# SCH_PIF_Line_Follower_2024-01-01_1.net
KiCad netlist of a schematic drawn in EasyEDA
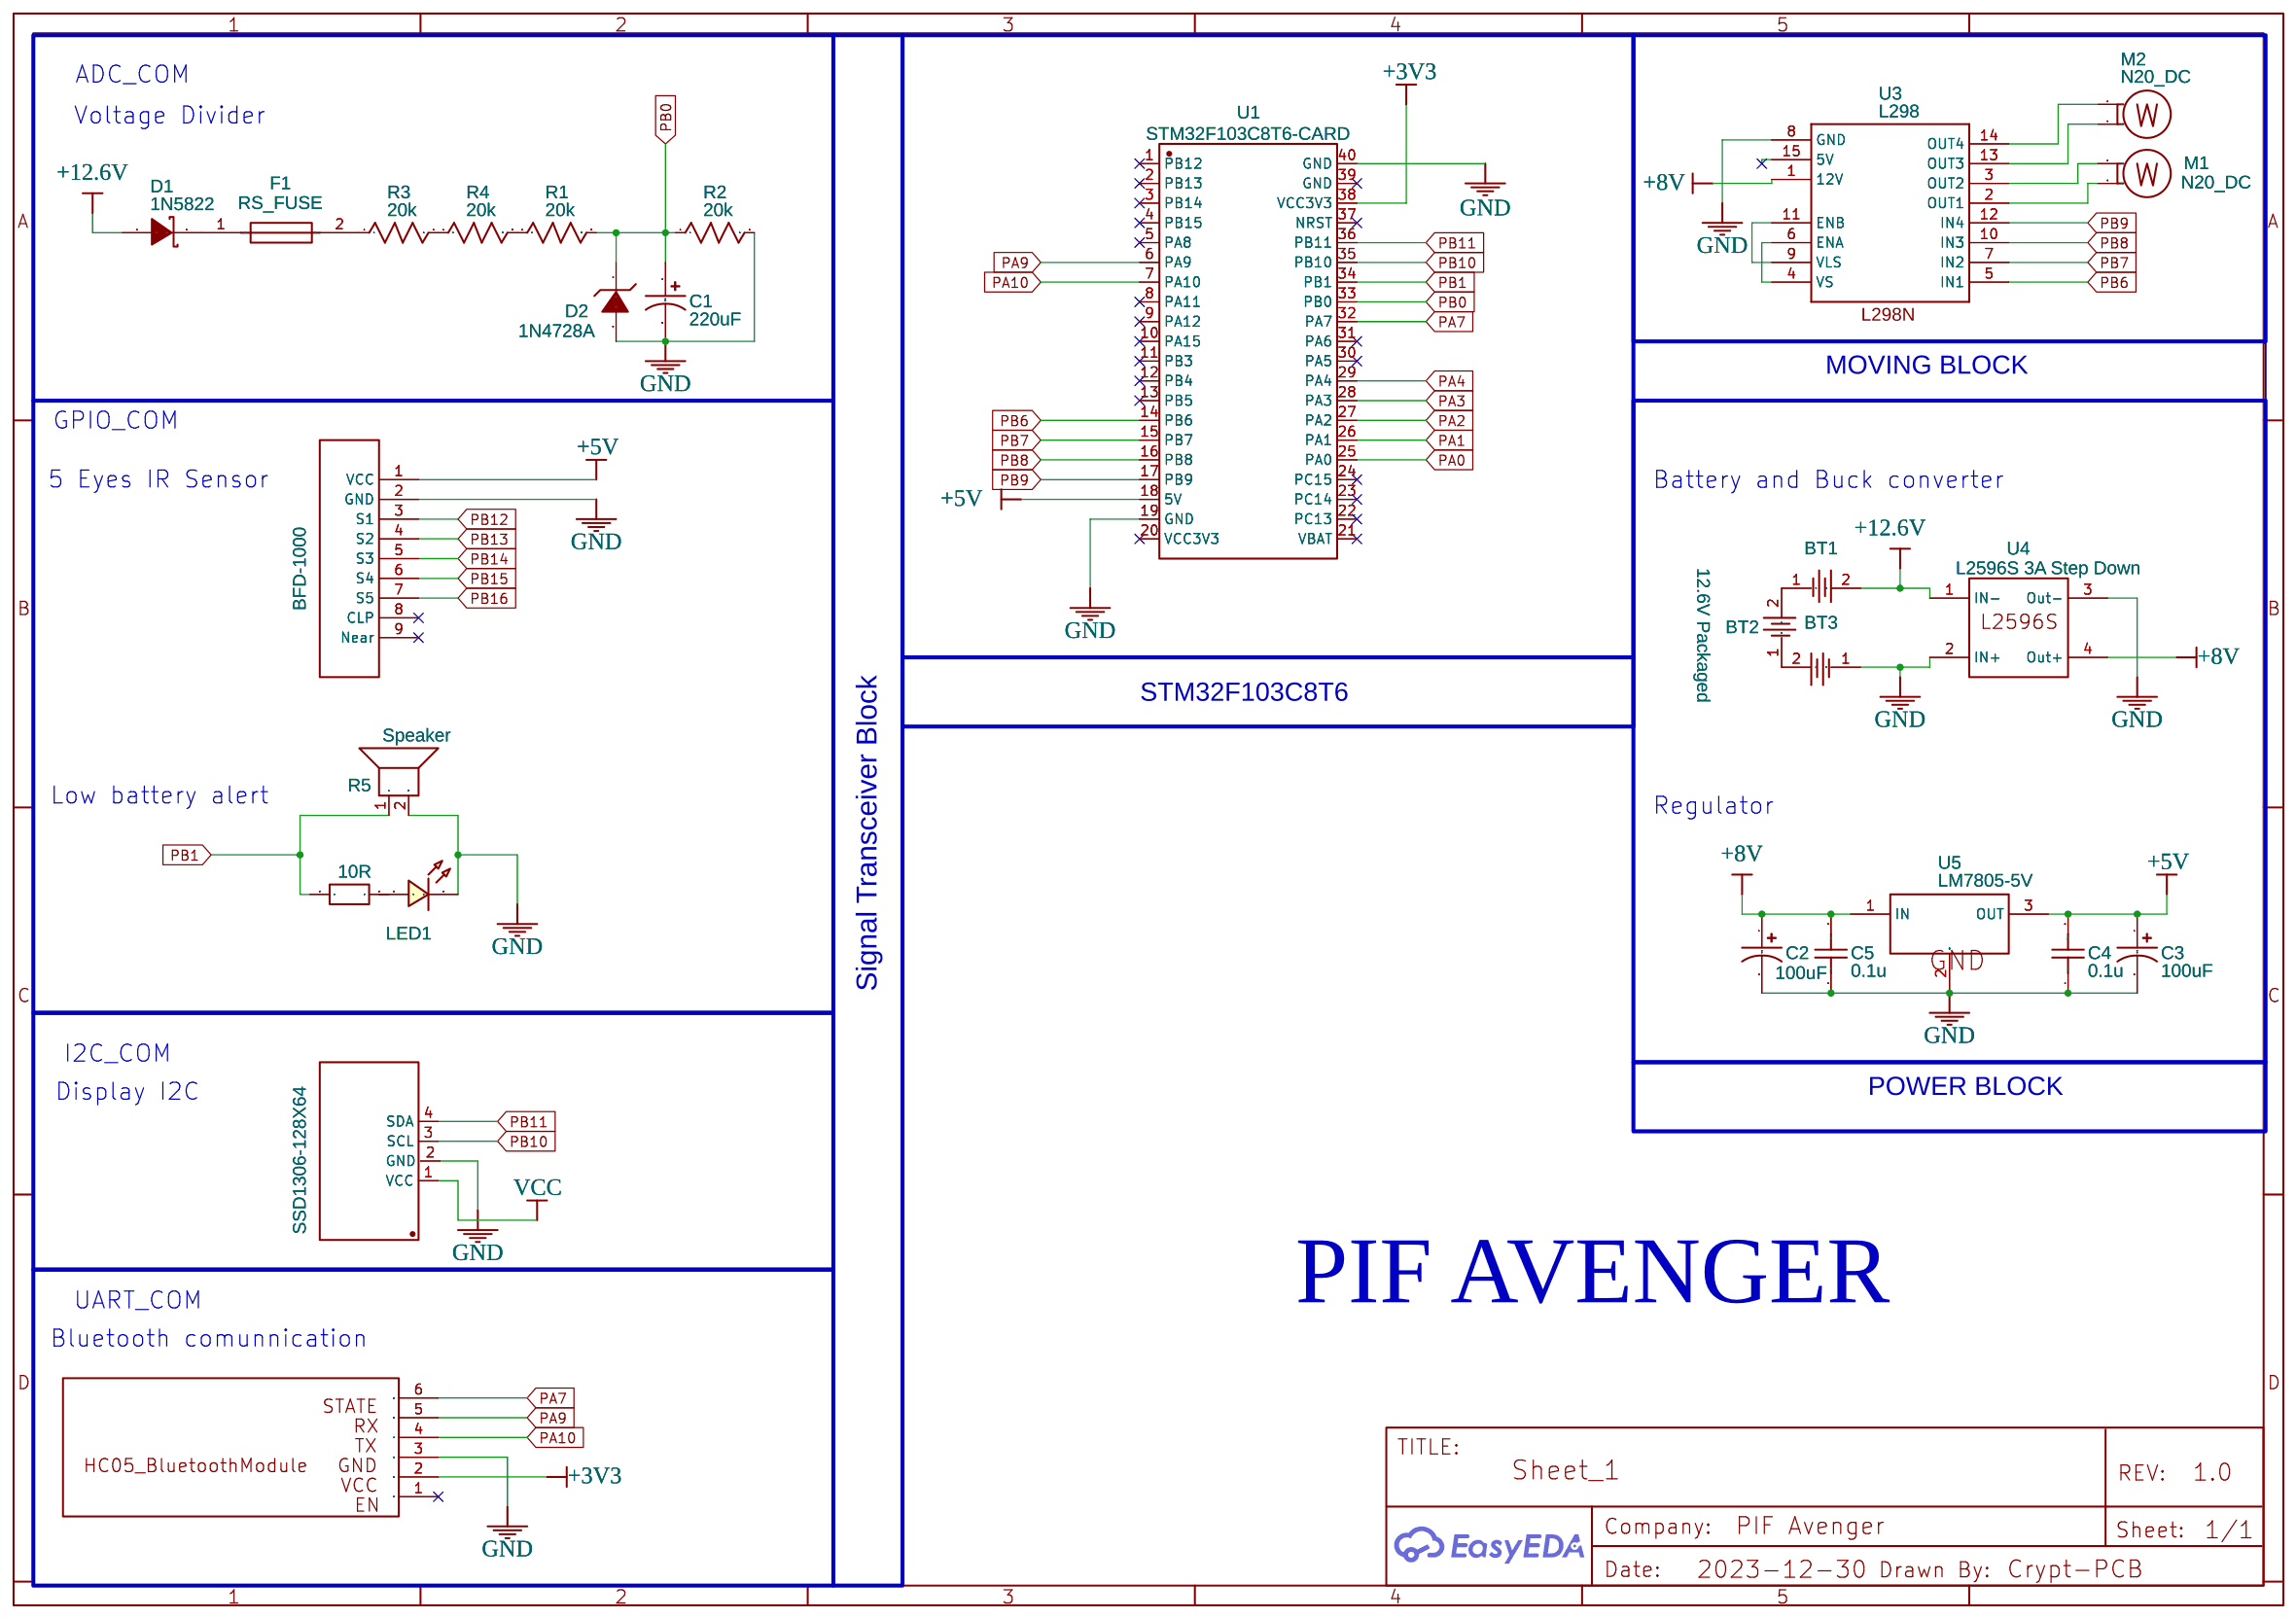
[diagram p0: schematic sheet]

(export (version "E")
  (design (tool "Eeschema 10.0.6"))
  (components
    (comp (ref "BT1")
      (value "BH-18650-A1AJ006")
      (fields (field (name "Manufacturer") "MYOUNG(美阳)"))
      (libsource (lib "") (part "BH-18650-A1AJ006_1"))
    )
    (comp (ref "BT2")
      (value "12.6V Packaged")
      (fields
        (field (name "Manufacturer Part") "BH-18650-A1AJ006")
        (field (name "Manufacturer") "MYOUNG(美阳)")
      )
      (libsource (lib "") (part "BH-18650-A1AJ006"))
    )
    (comp (ref "BT3")
      (value "BH-18650-A1AJ006")
      (fields (field (name "Manufacturer") "MYOUNG(美阳)"))
      (libsource (lib "") (part "BH-18650-A1AJ006_2"))
    )
    (comp (ref "C1") (value "220uF") (libsource (lib "") (part "CE_TH_D4.0×F1.5_US")))
    (comp (ref "C2") (value "100uF") (libsource (lib "") (part "CE_TH_D4.0×F1.5_US")))
    (comp (ref "C3") (value "100uF") (libsource (lib "") (part "CE_TH_D4.0×F1.5_US_1")))
    (comp (ref "C4") (value "0.1u") (libsource (lib "") (part "C_0603_US")))
    (comp (ref "C5") (value "0.1u") (libsource (lib "") (part "C_0603_US")))
    (comp (ref "D1")
      (value "1N5822")
      (fields (field (name "Manufacturer") "MDD"))
      (libsource (lib "") (part "1N5822"))
    )
    (comp (ref "D2")
      (value "1N4728A")
      (fields (field (name "Manufacturer") "onsemi(安森美)"))
      (libsource (lib "") (part "1N4728A_C140852"))
    )
    (comp (ref "F1")
      (value "RS_FUSE")
      (fields (field (name "Manufacturer Part") "ResettableFuse-500mA"))
      (libsource (lib "") (part "RESETTABLEFUSE-500MA"))
    )
    (comp (ref "LED1")
      (value "LED-0603_R")
      (fields
        (field (name "Manufacturer Part") "19-217/R6C-AL1M2VY/3T")
        (field (name "Manufacturer") "EVERLIGHT(台湾亿光)")
      )
      (libsource (lib "") (part "LED-0603_R"))
    )
    (comp (ref "LS1") (value "Speaker") (libsource (lib "") (part "Speaker")))
    (comp (ref "M1") (value "N20_DC") (libsource (lib "") (part "N20_DC")))
    (comp (ref "M2") (value "N20_DC") (libsource (lib "") (part "N20_DC")))
    (comp (ref "PCB1") (value "SSD1306-128X64") (libsource (lib "") (part "SSD1306-128X64-OLED-0.96 COPY")))
    (comp (ref "R1") (value "20k") (libsource (lib "") (part "R_0603_US")))
    (comp (ref "R2") (value "20k") (libsource (lib "") (part "R_0603_US")))
    (comp (ref "R3") (value "20k") (libsource (lib "") (part "R_0603_US")))
    (comp (ref "R4") (value "20k") (libsource (lib "") (part "R_0603_US")))
    (comp (ref "R5") (value "10R") (libsource (lib "") (part "R_0603_EU")))
    (comp (ref "U1")
      (value "STM32F103C8T6-CARD")
      (fields (field (name "Manufacturer Part") "STM32F103C8T6-Card"))
      (libsource (lib "") (part "STM32F103C8T6-CARD"))
    )
    (comp (ref "U2") (value "HC_05_Bluetooth") (libsource (lib "") (part "HC_05_Bluetooth")))
    (comp (ref "U3")
      (value "L298")
      (fields (field (name "Manufacturer Part") "L298N Driver"))
      (libsource (lib "") (part "L298"))
    )
    (comp (ref "U4") (value "L2596S 3A Step Down") (libsource (lib "") (part "L2596S 3A Step Down")))
    (comp (ref "U5") (value "LM7805-5V") (libsource (lib "") (part "LM7805-5V")))
    (comp (ref "U6") (value "BFD-1000") (libsource (lib "") (part "BFD-1000")))
  )
  (nets
    (net (code "1") (name "+3V3") (class "Default")
      (node (ref "U1") (pin "38") (pinfunction "VCC3V3_38") (pintype "unspecified"))
      (node (ref "U2") (pin "2") (pinfunction "2_2") (pintype "unspecified"))
    )
    (net (code "2") (name "+5V") (class "Default")
      (node (ref "C3") (pin "1") (pinfunction "1_1") (pintype "unspecified"))
      (node (ref "C4") (pin "2") (pinfunction "2_2") (pintype "unspecified"))
      (node (ref "U1") (pin "18") (pinfunction "5V_18") (pintype "unspecified"))
      (node (ref "U5") (pin "3") (pinfunction "OUT_3") (pintype "passive"))
      (node (ref "U6") (pin "1") (pinfunction "VCC_1") (pintype "passive"))
    )
    (net (code "3") (name "+8V") (class "Default")
      (node (ref "C2") (pin "1") (pinfunction "1_1") (pintype "unspecified"))
      (node (ref "C5") (pin "2") (pinfunction "2_2") (pintype "unspecified"))
      (node (ref "U3") (pin "1") (pinfunction "12V_1") (pintype "unspecified"))
      (node (ref "U4") (pin "4") (pinfunction "Out+_4") (pintype "unspecified"))
      (node (ref "U5") (pin "1") (pinfunction "IN_1") (pintype "passive"))
    )
    (net (code "4") (name "+12.6V") (class "Default")
      (node (ref "BT1") (pin "2") (pinfunction "2_2") (pintype "input"))
      (node (ref "D1") (pin "1") (pinfunction "A_1") (pintype "unspecified"))
      (node (ref "U4") (pin "1") (pinfunction "IN-_1") (pintype "unspecified"))
    )
    (net (code "5") (name "GND") (class "Default")
      (node (ref "BT3") (pin "1") (pinfunction "1_1") (pintype "input"))
      (node (ref "C1") (pin "2") (pinfunction "2_2") (pintype "unspecified"))
      (node (ref "C2") (pin "2") (pinfunction "2_2") (pintype "unspecified"))
      (node (ref "C3") (pin "2") (pinfunction "2_2") (pintype "unspecified"))
      (node (ref "C4") (pin "1") (pinfunction "1_1") (pintype "unspecified"))
      (node (ref "C5") (pin "1") (pinfunction "1_1") (pintype "unspecified"))
      (node (ref "D2") (pin "2") (pinfunction "A_2") (pintype "unspecified"))
      (node (ref "LED1") (pin "2") (pinfunction "2_2") (pintype "unspecified"))
      (node (ref "LS1") (pin "2") (pinfunction "2_2") (pintype "input"))
      (node (ref "PCB1") (pin "2") (pinfunction "GND_2") (pintype "input"))
      (node (ref "R2") (pin "2") (pinfunction "2_2") (pintype "unspecified"))
      (node (ref "U1") (pin "19") (pinfunction "GND_19") (pintype "unspecified"))
      (node (ref "U1") (pin "40") (pinfunction "GND_40") (pintype "unspecified"))
      (node (ref "U2") (pin "3") (pinfunction "3_3") (pintype "unspecified"))
      (node (ref "U3") (pin "8") (pinfunction "GND_8") (pintype "unspecified"))
      (node (ref "U4") (pin "2") (pinfunction "IN+_2") (pintype "unspecified"))
      (node (ref "U4") (pin "3") (pinfunction "Out-_3") (pintype "unspecified"))
      (node (ref "U5") (pin "2") (pinfunction "GND_2") (pintype "passive"))
      (node (ref "U6") (pin "2") (pinfunction "GND_2") (pintype "unspecified"))
    )
    (net (code "6") (name "Net-(BT1-Pad1)") (class "Default")
      (node (ref "BT1") (pin "1") (pinfunction "1_1") (pintype "input"))
      (node (ref "BT2") (pin "2") (pinfunction "2_2") (pintype "input"))
    )
    (net (code "7") (name "Net-(BT2-Pad1)") (class "Default")
      (node (ref "BT2") (pin "1") (pinfunction "1_1") (pintype "input"))
      (node (ref "BT3") (pin "2") (pinfunction "2_2") (pintype "input"))
    )
    (net (code "8") (name "Net-(D1-K)") (class "Default")
      (node (ref "D1") (pin "2") (pinfunction "K_2") (pintype "unspecified"))
      (node (ref "F1") (pin "1") (pinfunction "1_1") (pintype "unspecified"))
    )
    (net (code "9") (name "Net-(F1-Pad2)") (class "Default")
      (node (ref "F1") (pin "2") (pinfunction "2_2") (pintype "unspecified"))
      (node (ref "R3") (pin "1") (pinfunction "1_1") (pintype "unspecified"))
    )
    (net (code "10") (name "Net-(M1-+)") (class "Default")
      (node (ref "M1") (pin "2") (pinfunction "+_2") (pintype "unspecified"))
      (node (ref "U3") (pin "2") (pinfunction "OUT1_2") (pintype "unspecified"))
    )
    (net (code "11") (name "Net-(M1--)") (class "Default")
      (node (ref "M1") (pin "1") (pinfunction "-_1") (pintype "unspecified"))
      (node (ref "U3") (pin "3") (pinfunction "OUT2_3") (pintype "unspecified"))
    )
    (net (code "12") (name "Net-(M2-+)") (class "Default")
      (node (ref "M2") (pin "2") (pinfunction "+_2") (pintype "unspecified"))
      (node (ref "U3") (pin "13") (pinfunction "OUT3_13") (pintype "unspecified"))
    )
    (net (code "13") (name "Net-(M2--)") (class "Default")
      (node (ref "M2") (pin "1") (pinfunction "-_1") (pintype "unspecified"))
      (node (ref "U3") (pin "14") (pinfunction "OUT4_14") (pintype "unspecified"))
    )
    (net (code "14") (name "Net-(R1-Pad1)") (class "Default")
      (node (ref "R1") (pin "1") (pinfunction "1_1") (pintype "unspecified"))
      (node (ref "R4") (pin "2") (pinfunction "2_2") (pintype "unspecified"))
    )
    (net (code "15") (name "Net-(R3-Pad2)") (class "Default")
      (node (ref "R3") (pin "2") (pinfunction "2_2") (pintype "unspecified"))
      (node (ref "R4") (pin "1") (pinfunction "1_1") (pintype "unspecified"))
    )
    (net (code "16") (name "Net-(U3-ENA)") (class "Default")
      (node (ref "U3") (pin "4") (pinfunction "VS_4") (pintype "unspecified"))
      (node (ref "U3") (pin "6") (pinfunction "ENA_6") (pintype "unspecified"))
    )
    (net (code "17") (name "Net-(U3-ENB)") (class "Default")
      (node (ref "U3") (pin "11") (pinfunction "ENB_11") (pintype "unspecified"))
      (node (ref "U3") (pin "9") (pinfunction "VLS_9") (pintype "unspecified"))
    )
    (net (code "18") (name "PA0") (class "Default")
      (node (ref "U1") (pin "25") (pinfunction "PA0_25") (pintype "unspecified"))
    )
    (net (code "19") (name "PA1") (class "Default")
      (node (ref "U1") (pin "26") (pinfunction "PA1_26") (pintype "unspecified"))
    )
    (net (code "20") (name "PA2") (class "Default")
      (node (ref "U1") (pin "27") (pinfunction "PA2_27") (pintype "unspecified"))
    )
    (net (code "21") (name "PA3") (class "Default")
      (node (ref "U1") (pin "28") (pinfunction "PA3_28") (pintype "unspecified"))
    )
    (net (code "22") (name "PA4") (class "Default")
      (node (ref "U1") (pin "29") (pinfunction "PA4_29") (pintype "unspecified"))
    )
    (net (code "23") (name "PA7") (class "Default")
      (node (ref "U1") (pin "32") (pinfunction "PA7_32") (pintype "unspecified"))
      (node (ref "U2") (pin "6") (pinfunction "6_6") (pintype "unspecified"))
    )
    (net (code "24") (name "PA9") (class "Default")
      (node (ref "U1") (pin "6") (pinfunction "PA9_6") (pintype "unspecified"))
      (node (ref "U2") (pin "5") (pinfunction "5_5") (pintype "unspecified"))
    )
    (net (code "25") (name "PA10") (class "Default")
      (node (ref "U1") (pin "7") (pinfunction "PA10_7") (pintype "unspecified"))
      (node (ref "U2") (pin "4") (pinfunction "4_4") (pintype "unspecified"))
    )
    (net (code "26") (name "PB0") (class "Default")
      (node (ref "C1") (pin "1") (pinfunction "1_1") (pintype "unspecified"))
      (node (ref "D2") (pin "1") (pinfunction "K_1") (pintype "unspecified"))
      (node (ref "R1") (pin "2") (pinfunction "2_2") (pintype "unspecified"))
      (node (ref "R2") (pin "1") (pinfunction "1_1") (pintype "unspecified"))
      (node (ref "U1") (pin "33") (pinfunction "PB0_33") (pintype "unspecified"))
    )
    (net (code "27") (name "PB1") (class "Default")
      (node (ref "LS1") (pin "1") (pinfunction "1_1") (pintype "input"))
      (node (ref "R5") (pin "1") (pinfunction "1_1") (pintype "unspecified"))
      (node (ref "U1") (pin "34") (pinfunction "PB1_34") (pintype "unspecified"))
    )
    (net (code "28") (name "PB6") (class "Default")
      (node (ref "U1") (pin "14") (pinfunction "PB6_14") (pintype "unspecified"))
      (node (ref "U3") (pin "5") (pinfunction "IN1_5") (pintype "unspecified"))
    )
    (net (code "29") (name "PB7") (class "Default")
      (node (ref "U1") (pin "15") (pinfunction "PB7_15") (pintype "unspecified"))
      (node (ref "U3") (pin "7") (pinfunction "IN2_7") (pintype "unspecified"))
    )
    (net (code "30") (name "PB8") (class "Default")
      (node (ref "U1") (pin "16") (pinfunction "PB8_16") (pintype "unspecified"))
      (node (ref "U3") (pin "10") (pinfunction "IN3_10") (pintype "unspecified"))
    )
    (net (code "31") (name "PB9") (class "Default")
      (node (ref "U1") (pin "17") (pinfunction "PB9_17") (pintype "unspecified"))
      (node (ref "U3") (pin "12") (pinfunction "IN4_12") (pintype "unspecified"))
    )
    (net (code "32") (name "PB10") (class "Default")
      (node (ref "PCB1") (pin "3") (pinfunction "SCL_3") (pintype "passive"))
      (node (ref "U1") (pin "35") (pinfunction "PB10_35") (pintype "unspecified"))
    )
    (net (code "33") (name "PB11") (class "Default")
      (node (ref "PCB1") (pin "4") (pinfunction "SDA_4") (pintype "passive"))
      (node (ref "U1") (pin "36") (pinfunction "PB11_36") (pintype "unspecified"))
    )
    (net (code "34") (name "PB12") (class "Default")
      (node (ref "U6") (pin "3") (pinfunction "S1_3") (pintype "unspecified"))
    )
    (net (code "35") (name "PB13") (class "Default")
      (node (ref "U6") (pin "4") (pinfunction "S2_4") (pintype "unspecified"))
    )
    (net (code "36") (name "PB14") (class "Default")
      (node (ref "U6") (pin "5") (pinfunction "S3_5") (pintype "unspecified"))
    )
    (net (code "37") (name "PB15") (class "Default")
      (node (ref "U6") (pin "6") (pinfunction "S4_6") (pintype "unspecified"))
    )
    (net (code "38") (name "PB16") (class "Default")
      (node (ref "U6") (pin "7") (pinfunction "S5_7") (pintype "unspecified"))
    )
    (net (code "39") (name "VCC") (class "Default")
      (node (ref "PCB1") (pin "1") (pinfunction "VCC_1") (pintype "input"))
    )
    (net (code "40") (name "unconnected-(LED1-Pad1)") (class "Default")
      (node (ref "LED1") (pin "1") (pinfunction "1_1") (pintype "unspecified"))
    )
    (net (code "41") (name "unconnected-(R5-Pad2)") (class "Default")
      (node (ref "R5") (pin "2") (pinfunction "2_2") (pintype "unspecified"))
    )
    (net (code "42") (name "unconnected-(U1-GND-Pad39)") (class "Default")
      (node (ref "U1") (pin "39") (pinfunction "GND_39") (pintype "unspecified+no_connect"))
    )
    (net (code "43") (name "unconnected-(U1-NRST-Pad37)") (class "Default")
      (node (ref "U1") (pin "37") (pinfunction "NRST_37") (pintype "unspecified+no_connect"))
    )
    (net (code "44") (name "unconnected-(U1-PA5-Pad30)") (class "Default")
      (node (ref "U1") (pin "30") (pinfunction "PA5_30") (pintype "unspecified+no_connect"))
    )
    (net (code "45") (name "unconnected-(U1-PA6-Pad31)") (class "Default")
      (node (ref "U1") (pin "31") (pinfunction "PA6_31") (pintype "unspecified+no_connect"))
    )
    (net (code "46") (name "unconnected-(U1-PA8-Pad5)") (class "Default")
      (node (ref "U1") (pin "5") (pinfunction "PA8_5") (pintype "unspecified+no_connect"))
    )
    (net (code "47") (name "unconnected-(U1-PA11-Pad8)") (class "Default")
      (node (ref "U1") (pin "8") (pinfunction "PA11_8") (pintype "unspecified+no_connect"))
    )
    (net (code "48") (name "unconnected-(U1-PA12-Pad9)") (class "Default")
      (node (ref "U1") (pin "9") (pinfunction "PA12_9") (pintype "unspecified+no_connect"))
    )
    (net (code "49") (name "unconnected-(U1-PA15-Pad10)") (class "Default")
      (node (ref "U1") (pin "10") (pinfunction "PA15_10") (pintype "unspecified+no_connect"))
    )
    (net (code "50") (name "unconnected-(U1-PB3-Pad11)") (class "Default")
      (node (ref "U1") (pin "11") (pinfunction "PB3_11") (pintype "unspecified+no_connect"))
    )
    (net (code "51") (name "unconnected-(U1-PB4-Pad12)") (class "Default")
      (node (ref "U1") (pin "12") (pinfunction "PB4_12") (pintype "unspecified+no_connect"))
    )
    (net (code "52") (name "unconnected-(U1-PB5-Pad13)") (class "Default")
      (node (ref "U1") (pin "13") (pinfunction "PB5_13") (pintype "unspecified+no_connect"))
    )
    (net (code "53") (name "unconnected-(U1-PB12-Pad1)") (class "Default")
      (node (ref "U1") (pin "1") (pinfunction "PB12_1") (pintype "unspecified+no_connect"))
    )
    (net (code "54") (name "unconnected-(U1-PB13-Pad2)") (class "Default")
      (node (ref "U1") (pin "2") (pinfunction "PB13_2") (pintype "unspecified+no_connect"))
    )
    (net (code "55") (name "unconnected-(U1-PB14-Pad3)") (class "Default")
      (node (ref "U1") (pin "3") (pinfunction "PB14_3") (pintype "unspecified+no_connect"))
    )
    (net (code "56") (name "unconnected-(U1-PB15-Pad4)") (class "Default")
      (node (ref "U1") (pin "4") (pinfunction "PB15_4") (pintype "unspecified+no_connect"))
    )
    (net (code "57") (name "unconnected-(U1-PC13-Pad22)") (class "Default")
      (node (ref "U1") (pin "22") (pinfunction "PC13_22") (pintype "unspecified+no_connect"))
    )
    (net (code "58") (name "unconnected-(U1-PC14-Pad23)") (class "Default")
      (node (ref "U1") (pin "23") (pinfunction "PC14_23") (pintype "unspecified+no_connect"))
    )
    (net (code "59") (name "unconnected-(U1-PC15-Pad24)") (class "Default")
      (node (ref "U1") (pin "24") (pinfunction "PC15_24") (pintype "unspecified+no_connect"))
    )
    (net (code "60") (name "unconnected-(U1-VBAT-Pad21)") (class "Default")
      (node (ref "U1") (pin "21") (pinfunction "VBAT_21") (pintype "unspecified+no_connect"))
    )
    (net (code "61") (name "unconnected-(U1-VCC3V3-Pad20)") (class "Default")
      (node (ref "U1") (pin "20") (pinfunction "VCC3V3_20") (pintype "unspecified+no_connect"))
    )
    (net (code "62") (name "unconnected-(U2-Pad1)") (class "Default")
      (node (ref "U2") (pin "1") (pinfunction "1_1") (pintype "unspecified+no_connect"))
    )
    (net (code "63") (name "unconnected-(U3-5V-Pad15)") (class "Default")
      (node (ref "U3") (pin "15") (pinfunction "5V_15") (pintype "unspecified+no_connect"))
    )
    (net (code "64") (name "unconnected-(U6-CLP-Pad8)") (class "Default")
      (node (ref "U6") (pin "8") (pinfunction "CLP_8") (pintype "unspecified+no_connect"))
    )
    (net (code "65") (name "unconnected-(U6-Near-Pad9)") (class "Default")
      (node (ref "U6") (pin "9") (pinfunction "Near_9") (pintype "unspecified+no_connect"))
    )
  )
)
